# FlescherTow.net
KiCad netlist of a schematic drawn in Altium Designer
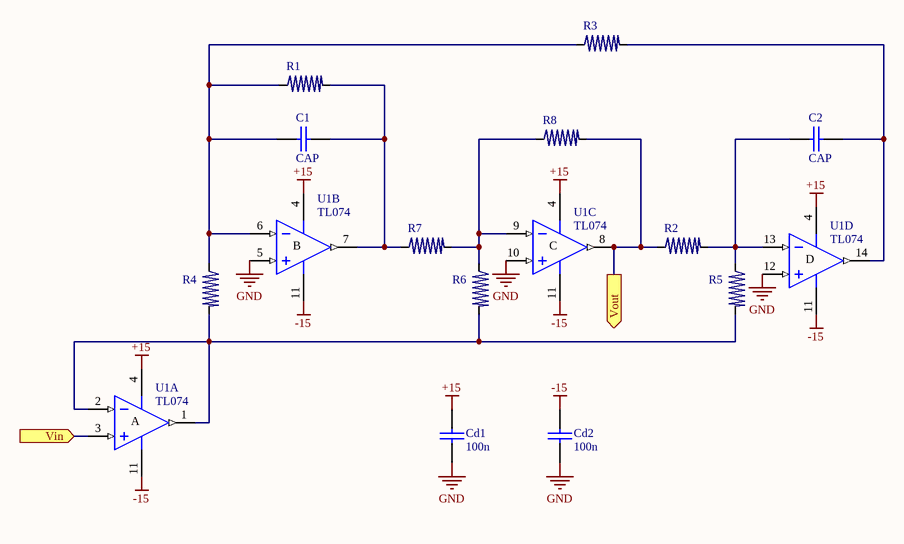
[diagram p0: FlescherTow.SchDoc]

(export (version "E")
  (design (tool "Eeschema 10.0.6"))
  (components
    (comp (ref "C1") (value "CAP") (footprint "0805") (libsource (lib "LIBEBAL") (part "CAP")))
    (comp (ref "C2") (value "CAP") (footprint "0805") (libsource (lib "LIBEBAL") (part "CAP")))
    (comp (ref "Cd1") (value "100n") (footprint "0805") (libsource (lib "LIBEBAL") (part "CAP")))
    (comp (ref "Cd2") (value "100n") (footprint "0805") (libsource (lib "LIBEBAL") (part "CAP")))
    (comp (ref "R1") (value "~") (footprint "PCBComponent_1") (libsource (lib "SPres") (part "SPres")))
    (comp (ref "R2") (value "~") (footprint "PCBComponent_1") (libsource (lib "SPres") (part "SPres")))
    (comp (ref "R3") (value "~") (footprint "PCBComponent_1") (libsource (lib "SPres") (part "SPres")))
    (comp (ref "R4") (value "~") (footprint "PCBComponent_1") (libsource (lib "SPres") (part "SPres")))
    (comp (ref "R5") (value "~") (footprint "PCBComponent_1") (libsource (lib "SPres") (part "SPres")))
    (comp (ref "R6") (value "~") (footprint "PCBComponent_1") (libsource (lib "SPres") (part "SPres")))
    (comp (ref "R7") (value "~") (footprint "PCBComponent_1") (libsource (lib "SPres") (part "SPres")))
    (comp (ref "R8") (value "~") (footprint "PCBComponent_1") (libsource (lib "SPres") (part "SPres")))
    (comp (ref "U1")
      (value "TL074")
      (footprint "J014")
      (description "Low-Noise JFET-Input Operational Amplifier")
      (fields (field (name "PUBLISHER") "Altium Limited"))
      (libsource (lib "TI Operational Amplifier") (part "TL074"))
    )
  )
  (nets
    (net (code "1") (name "+15") (class "Default")
      (node (ref "Cd1") (pin "1") (pinfunction "1_1") (pintype "passive"))
      (node (ref "U1") (pin "4") (pinfunction "V+_4") (pintype "power_in"))
    )
    (net (code "2") (name "-15") (class "Default")
      (node (ref "Cd2") (pin "1") (pinfunction "1_1") (pintype "passive"))
      (node (ref "U1") (pin "11") (pinfunction "V-_11") (pintype "power_in"))
    )
    (net (code "3") (name "/Vin") (class "Default")
      (node (ref "U1") (pin "3") (pinfunction "IN+_3") (pintype "input"))
    )
    (net (code "4") (name "/Vout") (class "Default")
      (node (ref "R2") (pin "2") (pinfunction "2_2") (pintype "passive"))
      (node (ref "R8") (pin "1") (pinfunction "1_1") (pintype "passive"))
      (node (ref "U1") (pin "8") (pinfunction "OUT_8") (pintype "output"))
    )
    (net (code "5") (name "GND") (class "Default")
      (node (ref "Cd1") (pin "2") (pinfunction "2_2") (pintype "passive"))
      (node (ref "Cd2") (pin "2") (pinfunction "2_2") (pintype "passive"))
      (node (ref "U1") (pin "10") (pinfunction "IN+_10") (pintype "input"))
      (node (ref "U1") (pin "12") (pinfunction "IN+_12") (pintype "input"))
      (node (ref "U1") (pin "5") (pinfunction "IN+_5") (pintype "input"))
    )
    (net (code "6") (name "Net-(U1A-IN-)") (class "Default")
      (node (ref "R4") (pin "1") (pinfunction "1_1") (pintype "passive"))
      (node (ref "R5") (pin "1") (pinfunction "1_1") (pintype "passive"))
      (node (ref "R6") (pin "1") (pinfunction "1_1") (pintype "passive"))
      (node (ref "U1") (pin "1") (pinfunction "OUT_1") (pintype "output"))
      (node (ref "U1") (pin "2") (pinfunction "IN-_2") (pintype "input"))
    )
    (net (code "7") (name "Net-(U1B-IN-)") (class "Default")
      (node (ref "C1") (pin "1") (pinfunction "1_1") (pintype "passive"))
      (node (ref "R1") (pin "2") (pinfunction "2_2") (pintype "passive"))
      (node (ref "R3") (pin "2") (pinfunction "2_2") (pintype "passive"))
      (node (ref "R4") (pin "2") (pinfunction "2_2") (pintype "passive"))
      (node (ref "U1") (pin "6") (pinfunction "IN-_6") (pintype "input"))
    )
    (net (code "8") (name "Net-(U1B-OUT)") (class "Default")
      (node (ref "C1") (pin "2") (pinfunction "2_2") (pintype "passive"))
      (node (ref "R1") (pin "1") (pinfunction "1_1") (pintype "passive"))
      (node (ref "R7") (pin "2") (pinfunction "2_2") (pintype "passive"))
      (node (ref "U1") (pin "7") (pinfunction "OUT_7") (pintype "output"))
    )
    (net (code "9") (name "Net-(U1C-IN-)") (class "Default")
      (node (ref "R6") (pin "2") (pinfunction "2_2") (pintype "passive"))
      (node (ref "R7") (pin "1") (pinfunction "1_1") (pintype "passive"))
      (node (ref "R8") (pin "2") (pinfunction "2_2") (pintype "passive"))
      (node (ref "U1") (pin "9") (pinfunction "IN-_9") (pintype "input"))
    )
    (net (code "10") (name "Net-(U1D-IN-)") (class "Default")
      (node (ref "C2") (pin "1") (pinfunction "1_1") (pintype "passive"))
      (node (ref "R2") (pin "1") (pinfunction "1_1") (pintype "passive"))
      (node (ref "R5") (pin "2") (pinfunction "2_2") (pintype "passive"))
      (node (ref "U1") (pin "13") (pinfunction "IN-_13") (pintype "input"))
    )
    (net (code "11") (name "Net-(U1D-OUT)") (class "Default")
      (node (ref "C2") (pin "2") (pinfunction "2_2") (pintype "passive"))
      (node (ref "R3") (pin "1") (pinfunction "1_1") (pintype "passive"))
      (node (ref "U1") (pin "14") (pinfunction "OUT_14") (pintype "output"))
    )
  )
)
